# Microcontroller.net
KiCad netlist of a schematic drawn in Altium Designer
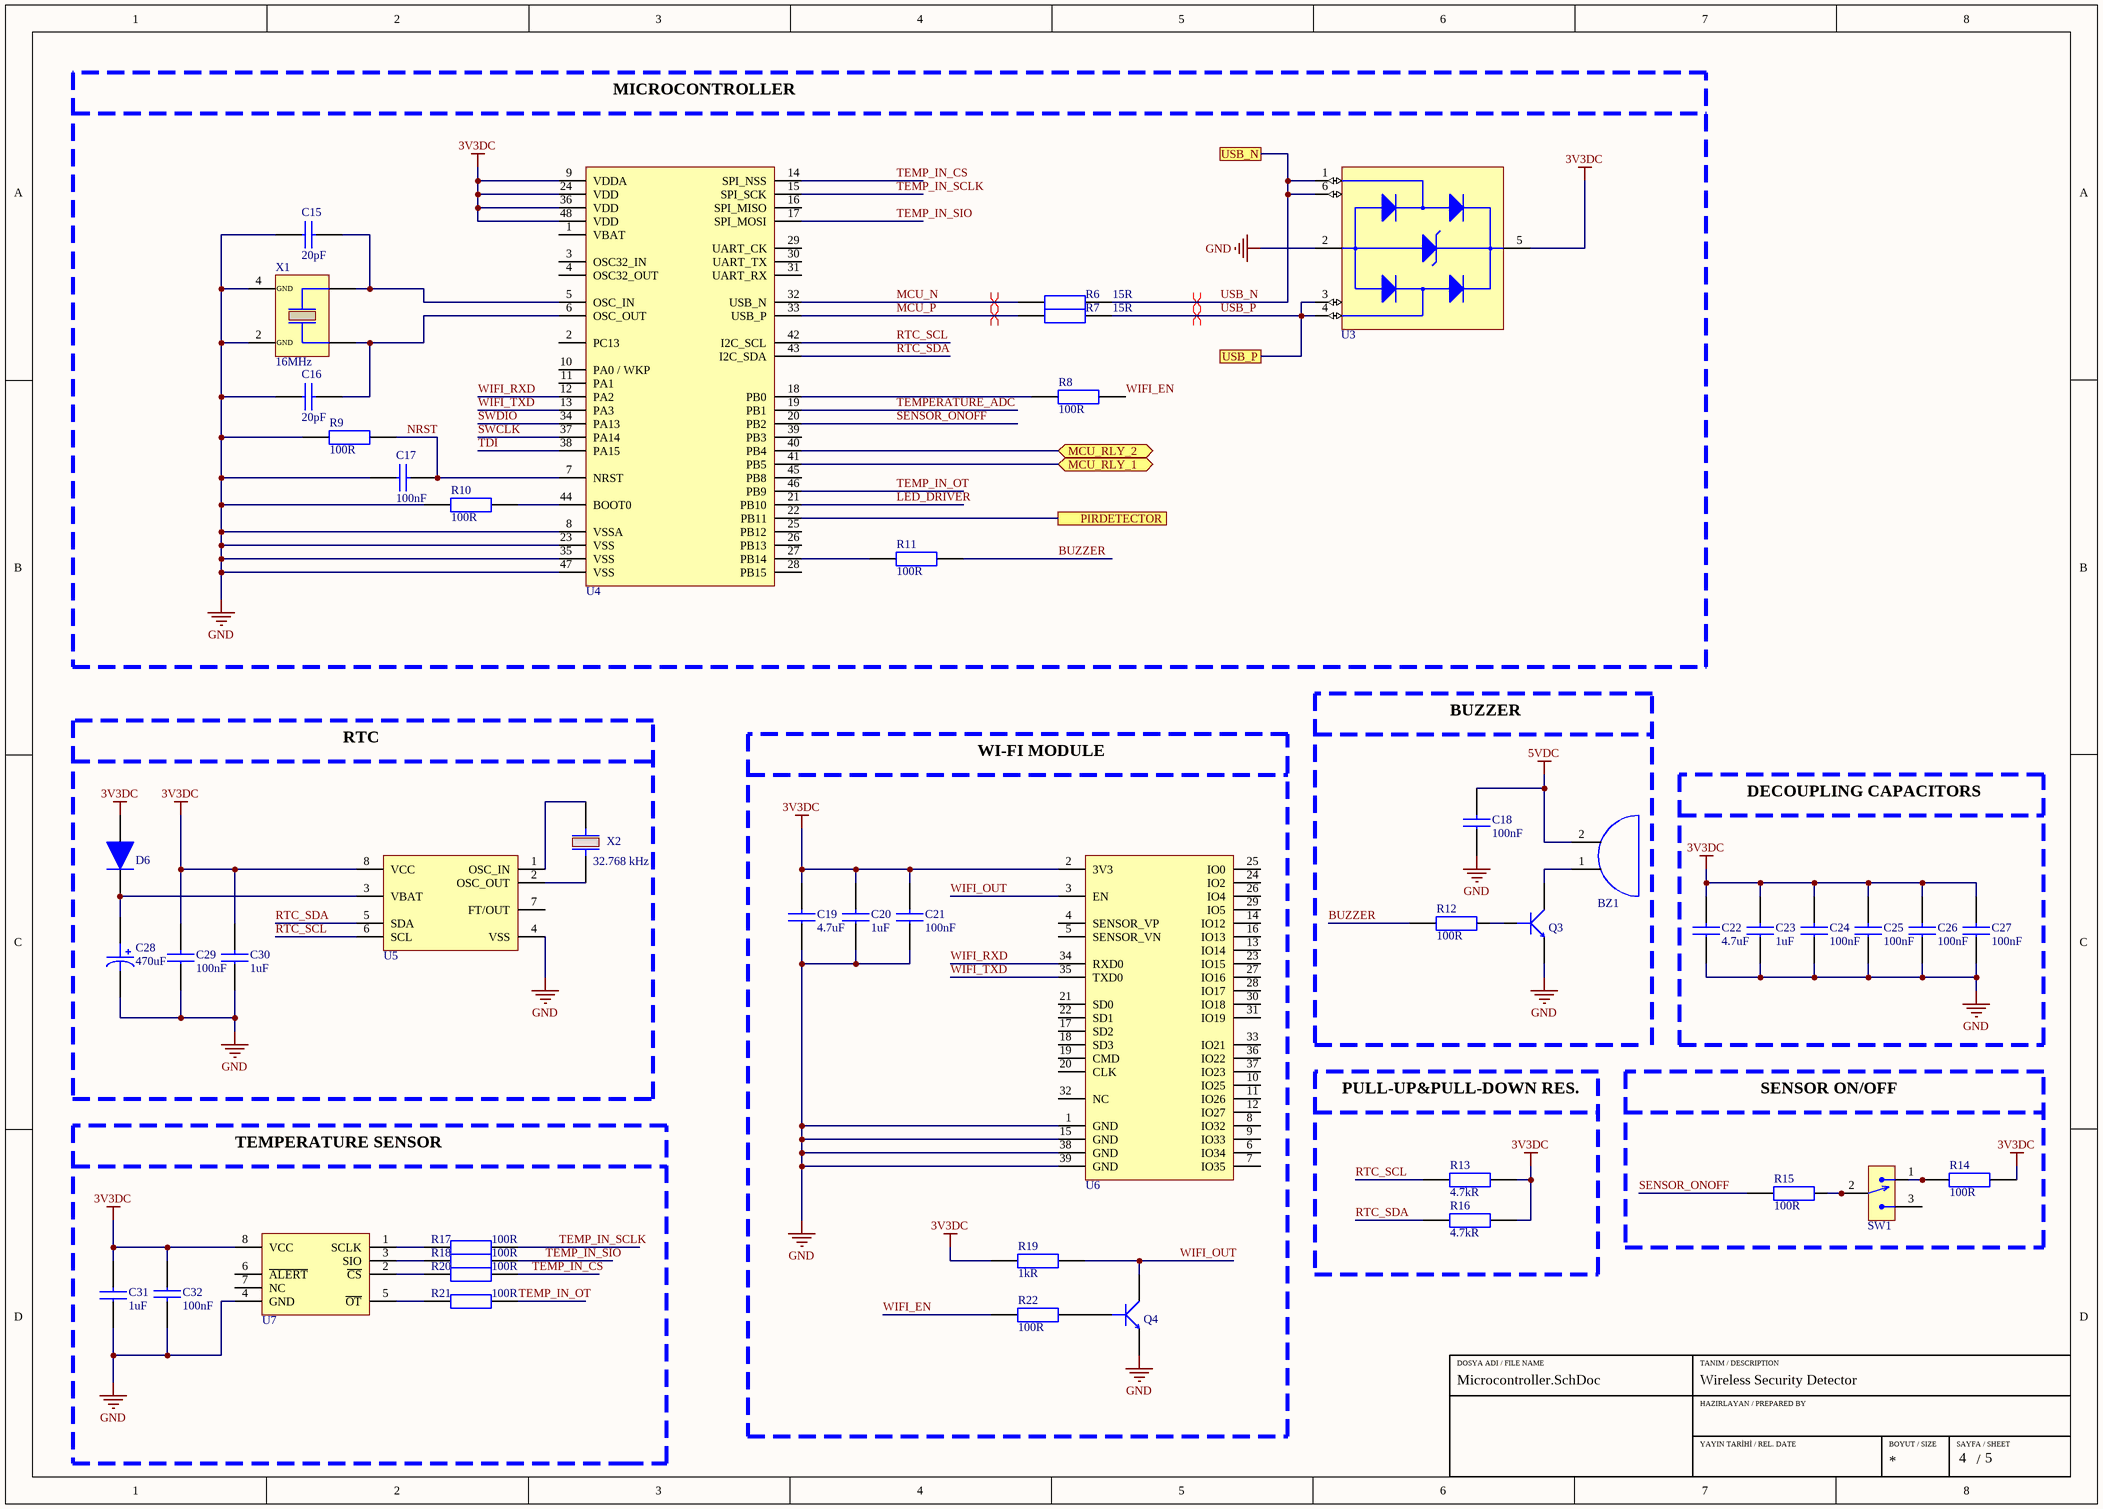
[diagram p0: Microcontroller.SchDoc]

(export (version "E")
  (design (tool "Eeschema 10.0.6"))
  (components
    (comp (ref "BZ1")
      (value "CMI-9605IC-0580T")
      (footprint "CMI-9605IC")
      (description "Buzzers Indicator, Internally Driven Magnetic 5V 30mA 2.7kHz 80dB @ 5V, 10cm Through Hole PC Pins")
      (fields (field (name "MANUFACTURER") "CUI Devices") (field (name "DESIGNED BY") "BERK"))
      (libsource (lib "SECURITY_CAM") (part "CMI-9605IC-0580T"))
    )
    (comp (ref "C15")
      (value "CL10C200JB8NNNC")
      (footprint "CAP_0603")
      (description "CAP CER 20pF %5 0603 SMD")
      (fields
        (field (name "MANUFACTURER") "Samsung")
        (field (name "TOLERANCE") "5%")
        (field (name "CAPACITANCE") "20pF")
        (field (name "DESIGNED BY") "BERK")
      )
      (libsource (lib "SECURITY_CAM") (part "CAP CER 20pF 0603"))
    )
    (comp (ref "C16")
      (value "CL10C200JB8NNNC")
      (footprint "CAP_0603")
      (description "CAP CER 20pF %5 0603 SMD")
      (fields
        (field (name "MANUFACTURER") "Samsung")
        (field (name "TOLERANCE") "5%")
        (field (name "CAPACITANCE") "20pF")
        (field (name "DESIGNED BY") "BERK")
      )
      (libsource (lib "SECURITY_CAM") (part "CAP CER 20pF 0603"))
    )
    (comp (ref "C17")
      (value "C0603C104K5RACTU")
      (footprint "CAP_0603")
      (description "CAP CER 100nF %10 0603 SMD")
      (fields
        (field (name "MANUFACTURER") "KEMET")
        (field (name "TOLERANCE") "10%")
        (field (name "CAPACITANCE") "100nF")
        (field (name "DESIGNED BY") "BERK")
      )
      (libsource (lib "SECURITY_CAM") (part "CAP CER 100nF 0603"))
    )
    (comp (ref "C18")
      (value "CL21B104KBCNNNC")
      (footprint "CAP_0805")
      (description "CAP CER 100nF %10 0805")
      (fields
        (field (name "MANUFACTURER") "Samsung")
        (field (name "TOLERANCE") "10%")
        (field (name "CAPACITANCE") "100nF")
        (field (name "DESIGNED BY") "BERK")
      )
      (libsource (lib "SECURITY_CAM") (part "CAP CER 100nF 0805"))
    )
    (comp (ref "C19")
      (value "CL21A475KAQNNNE")
      (footprint "CAP_0805")
      (description "CAP CER 4.7uF %10 0805")
      (fields
        (field (name "MANUFACTURER") "Samsung")
        (field (name "TOLERANCE") "10%")
        (field (name "CAPACITANCE") "4.7uF")
        (field (name "DESIGNED BY") "BERK")
      )
      (libsource (lib "SECURITY_CAM") (part "CAP CER 4.7uF 0805"))
    )
    (comp (ref "C20")
      (value "CL21B105KBFNNNE")
      (footprint "CAP_0805")
      (description "CAP CER 1uF %10 0805")
      (fields
        (field (name "MANUFACTURER") "Samsung")
        (field (name "TOLERANCE") "10%")
        (field (name "CAPACITANCE") "1uF")
        (field (name "DESIGNED BY") "BERK")
      )
      (libsource (lib "SECURITY_CAM") (part "CAP CER 1uF 0805"))
    )
    (comp (ref "C21")
      (value "CL21B104KBCNNNC")
      (footprint "CAP_0805")
      (description "CAP CER 100nF %10 0805")
      (fields
        (field (name "MANUFACTURER") "Samsung")
        (field (name "TOLERANCE") "10%")
        (field (name "CAPACITANCE") "100nF")
        (field (name "DESIGNED BY") "BERK")
      )
      (libsource (lib "SECURITY_CAM") (part "CAP CER 100nF 0805"))
    )
    (comp (ref "C22")
      (value "CL21A475KAQNNNE")
      (footprint "CAP_0805")
      (description "CAP CER 4.7uF %10 0805")
      (fields
        (field (name "MANUFACTURER") "Samsung")
        (field (name "TOLERANCE") "10%")
        (field (name "CAPACITANCE") "4.7uF")
        (field (name "DESIGNED BY") "BERK")
      )
      (libsource (lib "SECURITY_CAM") (part "CAP CER 4.7uF 0805"))
    )
    (comp (ref "C23")
      (value "CL21B105KBFNNNE")
      (footprint "CAP_0805")
      (description "CAP CER 1uF %10 0805")
      (fields
        (field (name "MANUFACTURER") "Samsung")
        (field (name "TOLERANCE") "10%")
        (field (name "CAPACITANCE") "1uF")
        (field (name "DESIGNED BY") "BERK")
      )
      (libsource (lib "SECURITY_CAM") (part "CAP CER 1uF 0805"))
    )
    (comp (ref "C24")
      (value "C0603C104K5RACTU")
      (footprint "CAP_0603")
      (description "CAP CER 100nF %10 0603 SMD")
      (fields
        (field (name "MANUFACTURER") "KEMET")
        (field (name "TOLERANCE") "10%")
        (field (name "CAPACITANCE") "100nF")
        (field (name "DESIGNED BY") "BERK")
      )
      (libsource (lib "SECURITY_CAM") (part "CAP CER 100nF 0603"))
    )
    (comp (ref "C25")
      (value "C0603C104K5RACTU")
      (footprint "CAP_0603")
      (description "CAP CER 100nF %10 0603 SMD")
      (fields
        (field (name "MANUFACTURER") "KEMET")
        (field (name "TOLERANCE") "10%")
        (field (name "CAPACITANCE") "100nF")
        (field (name "DESIGNED BY") "BERK")
      )
      (libsource (lib "SECURITY_CAM") (part "CAP CER 100nF 0603"))
    )
    (comp (ref "C26")
      (value "C0603C104K5RACTU")
      (footprint "CAP_0603")
      (description "CAP CER 100nF %10 0603 SMD")
      (fields
        (field (name "MANUFACTURER") "KEMET")
        (field (name "TOLERANCE") "10%")
        (field (name "CAPACITANCE") "100nF")
        (field (name "DESIGNED BY") "BERK")
      )
      (libsource (lib "SECURITY_CAM") (part "CAP CER 100nF 0603"))
    )
    (comp (ref "C27")
      (value "C0603C104K5RACTU")
      (footprint "CAP_0603")
      (description "CAP CER 100nF %10 0603 SMD")
      (fields
        (field (name "MANUFACTURER") "KEMET")
        (field (name "TOLERANCE") "10%")
        (field (name "CAPACITANCE") "100nF")
        (field (name "DESIGNED BY") "BERK")
      )
      (libsource (lib "SECURITY_CAM") (part "CAP CER 100nF 0603"))
    )
    (comp (ref "C28")
      (value "ESH477M050AH4AA")
      (footprint "CAP_RADIAL_D10_P5")
      (description "CAP ALU ELEC 470uF 50V RADIAL")
      (fields
        (field (name "MANUFACTURER") "KEMET")
        (field (name "TOLERANCE") "20%")
        (field (name "CAPACITANCE") "470uF")
        (field (name "DESIGNED BY") "BERK")
      )
      (libsource (lib "SECURITY_CAM") (part "CAP ALU ELEC 470uF 50V"))
    )
    (comp (ref "C29")
      (value "CL21B104KBCNNNC")
      (footprint "CAP_0805")
      (description "CAP CER 100nF %10 0805")
      (fields
        (field (name "MANUFACTURER") "Samsung")
        (field (name "TOLERANCE") "10%")
        (field (name "CAPACITANCE") "100nF")
        (field (name "DESIGNED BY") "BERK")
      )
      (libsource (lib "SECURITY_CAM") (part "CAP CER 100nF 0805"))
    )
    (comp (ref "C30")
      (value "CL21B105KBFNNNE")
      (footprint "CAP_0805")
      (description "CAP CER 1uF %10 0805")
      (fields
        (field (name "MANUFACTURER") "Samsung")
        (field (name "TOLERANCE") "10%")
        (field (name "CAPACITANCE") "1uF")
        (field (name "DESIGNED BY") "BERK")
      )
      (libsource (lib "SECURITY_CAM") (part "CAP CER 1uF 0805"))
    )
    (comp (ref "C31")
      (value "CL21B105KBFNNNE")
      (footprint "CAP_0805")
      (description "CAP CER 1uF %10 0805")
      (fields
        (field (name "MANUFACTURER") "Samsung")
        (field (name "TOLERANCE") "10%")
        (field (name "CAPACITANCE") "1uF")
        (field (name "DESIGNED BY") "BERK")
      )
      (libsource (lib "SECURITY_CAM") (part "CAP CER 1uF 0805"))
    )
    (comp (ref "C32")
      (value "CL21B104KBCNNNC")
      (footprint "CAP_0805")
      (description "CAP CER 100nF %10 0805")
      (fields
        (field (name "MANUFACTURER") "Samsung")
        (field (name "TOLERANCE") "10%")
        (field (name "CAPACITANCE") "100nF")
        (field (name "DESIGNED BY") "BERK")
      )
      (libsource (lib "SECURITY_CAM") (part "CAP CER 100nF 0805"))
    )
    (comp (ref "D6")
      (value "1N4148WS")
      (footprint "SOD323F")
      (description "Diode, Single, 75 V, 150 mA, 1 V, 4 ns")
      (fields
        (field (name "MANUFACTURER") "ON Semiconductor / Fairchild")
        (field (name "DESIGNED BY") "BERK")
      )
      (libsource (lib "SECURITY_CAM") (part "1N4148WS"))
    )
    (comp (ref "Q3")
      (value "MMBT3904-7-F")
      (footprint "SOT-23F")
      (description "Transistor General Purpose BJT NPN 40 Volt 0.2A Automotive 3-Pin SOT-23")
      (fields (field (name "MANUFACTURER") "Diodes Zetex") (field (name "DESIGNED BY") "BERK"))
      (libsource (lib "SECURITY_CAM") (part "MMBT3904-7-F"))
    )
    (comp (ref "Q4")
      (value "MMBT3904-7-F")
      (footprint "SOT-23F")
      (description "Transistor General Purpose BJT NPN 40 Volt 0.2A Automotive 3-Pin SOT-23")
      (fields (field (name "MANUFACTURER") "Diodes Zetex") (field (name "DESIGNED BY") "BERK"))
      (libsource (lib "SECURITY_CAM") (part "MMBT3904-7-F"))
    )
    (comp (ref "R6")
      (value "RC0603JR-0715RL")
      (footprint "RES_0603")
      (description "RES 15 %5 OHM 0603 SMD")
      (fields
        (field (name "MANUFACTURER") "Yageo")
        (field (name "TOLERANCE") "5%")
        (field (name "RESISTANCE") "15R")
        (field (name "DESIGNED BY") "BERK")
      )
      (libsource (lib "SECURITY_CAM") (part "RES 15 OHM 0603"))
    )
    (comp (ref "R7")
      (value "RC0603JR-0715RL")
      (footprint "RES_0603")
      (description "RES 15 %5 OHM 0603 SMD")
      (fields
        (field (name "MANUFACTURER") "Yageo")
        (field (name "TOLERANCE") "5%")
        (field (name "RESISTANCE") "15R")
        (field (name "DESIGNED BY") "BERK")
      )
      (libsource (lib "SECURITY_CAM") (part "RES 15 OHM 0603"))
    )
    (comp (ref "R8")
      (value "RC0603JR-07100RL")
      (footprint "RES_0603")
      (description "RES 100 %5 OHM 0603 SMD")
      (fields
        (field (name "MANUFACTURER") "Yageo")
        (field (name "TOLERANCE") "5%")
        (field (name "RESISTANCE") "100R")
        (field (name "DESIGNED BY") "BERK")
      )
      (libsource (lib "SECURITY_CAM") (part "RES 100 OHM 0603"))
    )
    (comp (ref "R9")
      (value "RC0603JR-07100RL")
      (footprint "RES_0603")
      (description "RES 100 %5 OHM 0603 SMD")
      (fields
        (field (name "MANUFACTURER") "Yageo")
        (field (name "TOLERANCE") "5%")
        (field (name "RESISTANCE") "100R")
        (field (name "DESIGNED BY") "BERK")
      )
      (libsource (lib "SECURITY_CAM") (part "RES 100 OHM 0603"))
    )
    (comp (ref "R10")
      (value "RC0603JR-07100RL")
      (footprint "RES_0603")
      (description "RES 100 %5 OHM 0603 SMD")
      (fields
        (field (name "MANUFACTURER") "Yageo")
        (field (name "TOLERANCE") "5%")
        (field (name "RESISTANCE") "100R")
        (field (name "DESIGNED BY") "BERK")
      )
      (libsource (lib "SECURITY_CAM") (part "RES 100 OHM 0603"))
    )
    (comp (ref "R11")
      (value "RC0603JR-07100RL")
      (footprint "RES_0603")
      (description "RES 100 %5 OHM 0603 SMD")
      (fields
        (field (name "MANUFACTURER") "Yageo")
        (field (name "TOLERANCE") "5%")
        (field (name "RESISTANCE") "100R")
        (field (name "DESIGNED BY") "BERK")
      )
      (libsource (lib "SECURITY_CAM") (part "RES 100 OHM 0603"))
    )
    (comp (ref "R12")
      (value "RC0603JR-07100RL")
      (footprint "RES_0603")
      (description "RES 100 %5 OHM 0603 SMD")
      (fields
        (field (name "MANUFACTURER") "Yageo")
        (field (name "TOLERANCE") "5%")
        (field (name "RESISTANCE") "100R")
        (field (name "DESIGNED BY") "BERK")
      )
      (libsource (lib "SECURITY_CAM") (part "RES 100 OHM 0603"))
    )
    (comp (ref "R13")
      (value "RC0603JR-074K7L")
      (footprint "RES_0603")
      (description "RES 4K7 %5 OHM 0603 SMD")
      (fields
        (field (name "MANUFACTURER") "Yageo")
        (field (name "TOLERANCE") "5%")
        (field (name "RESISTANCE") "4.7kR")
        (field (name "DESIGNED BY") "BERK")
      )
      (libsource (lib "SECURITY_CAM") (part "RES 4K7 OHM 0603"))
    )
    (comp (ref "R14")
      (value "RC0603JR-07100RL")
      (footprint "RES_0603")
      (description "RES 100 %5 OHM 0603 SMD")
      (fields
        (field (name "MANUFACTURER") "Yageo")
        (field (name "TOLERANCE") "5%")
        (field (name "RESISTANCE") "100R")
        (field (name "DESIGNED BY") "BERK")
      )
      (libsource (lib "SECURITY_CAM") (part "RES 100 OHM 0603"))
    )
    (comp (ref "R15")
      (value "RC0603JR-07100RL")
      (footprint "RES_0603")
      (description "RES 100 %5 OHM 0603 SMD")
      (fields
        (field (name "MANUFACTURER") "Yageo")
        (field (name "TOLERANCE") "5%")
        (field (name "RESISTANCE") "100R")
        (field (name "DESIGNED BY") "BERK")
      )
      (libsource (lib "SECURITY_CAM") (part "RES 100 OHM 0603"))
    )
    (comp (ref "R16")
      (value "RC0603JR-074K7L")
      (footprint "RES_0603")
      (description "RES 4K7 %5 OHM 0603 SMD")
      (fields
        (field (name "MANUFACTURER") "Yageo")
        (field (name "TOLERANCE") "5%")
        (field (name "RESISTANCE") "4.7kR")
        (field (name "DESIGNED BY") "BERK")
      )
      (libsource (lib "SECURITY_CAM") (part "RES 4K7 OHM 0603"))
    )
    (comp (ref "R17")
      (value "RC0603JR-07100RL")
      (footprint "RES_0603")
      (description "RES 100 %5 OHM 0603 SMD")
      (fields
        (field (name "MANUFACTURER") "Yageo")
        (field (name "TOLERANCE") "5%")
        (field (name "RESISTANCE") "100R")
        (field (name "DESIGNED BY") "BERK")
      )
      (libsource (lib "SECURITY_CAM") (part "RES 100 OHM 0603"))
    )
    (comp (ref "R18")
      (value "RC0603JR-07100RL")
      (footprint "RES_0603")
      (description "RES 100 %5 OHM 0603 SMD")
      (fields
        (field (name "MANUFACTURER") "Yageo")
        (field (name "TOLERANCE") "5%")
        (field (name "RESISTANCE") "100R")
        (field (name "DESIGNED BY") "BERK")
      )
      (libsource (lib "SECURITY_CAM") (part "RES 100 OHM 0603"))
    )
    (comp (ref "R19")
      (value "RC0603FR-0710KL")
      (footprint "RES_0603")
      (description "RES 1K %1 OHM 0603 SMD")
      (fields
        (field (name "MANUFACTURER") "Yageo")
        (field (name "MANUFACTURER PART NUMBER") "RC0603JR-071KL")
        (field (name "RESISTANCE") "1kR")
        (field (name "DESIGNED BY") "BERK")
      )
      (libsource (lib "SECURITY_CAM") (part "RES 1K OHM 0603"))
    )
    (comp (ref "R20")
      (value "RC0603JR-07100RL")
      (footprint "RES_0603")
      (description "RES 100 %5 OHM 0603 SMD")
      (fields
        (field (name "MANUFACTURER") "Yageo")
        (field (name "TOLERANCE") "5%")
        (field (name "RESISTANCE") "100R")
        (field (name "DESIGNED BY") "BERK")
      )
      (libsource (lib "SECURITY_CAM") (part "RES 100 OHM 0603"))
    )
    (comp (ref "R21")
      (value "RC0603JR-07100RL")
      (footprint "RES_0603")
      (description "RES 100 %5 OHM 0603 SMD")
      (fields
        (field (name "MANUFACTURER") "Yageo")
        (field (name "TOLERANCE") "5%")
        (field (name "RESISTANCE") "100R")
        (field (name "DESIGNED BY") "BERK")
      )
      (libsource (lib "SECURITY_CAM") (part "RES 100 OHM 0603"))
    )
    (comp (ref "R22")
      (value "RC0603JR-07100RL")
      (footprint "RES_0603")
      (description "RES 100 %5 OHM 0603 SMD")
      (fields
        (field (name "MANUFACTURER") "Yageo")
        (field (name "TOLERANCE") "5%")
        (field (name "RESISTANCE") "100R")
        (field (name "DESIGNED BY") "BERK")
      )
      (libsource (lib "SECURITY_CAM") (part "RES 100 OHM 0603"))
    )
    (comp (ref "SW1")
      (value "EG1215AA")
      (footprint "EG1215AA")
      (description "Slide Switch, SPDT, 0.025A, 24V, SMD")
      (fields
        (field (name "MANUFACTURER") "E-Switch")
        (field (name "TOLERANCE") "4.95%")
        (field (name "DESIGNED BY") "BERK")
      )
      (libsource (lib "SECURITY_CAM") (part "EG1215AA"))
    )
    (comp (ref "U3")
      (value "USBLC6-2SC6")
      (footprint "SOT23-6L")
      (description "TVS DIODE 5.25V 17V SOT23-6")
      (fields (field (name "MANUFACTURER") "STMicroelectronics") (field (name "DESIGNED BY") "BERK"))
      (libsource (lib "SECURITY_CAM") (part "USB PROTECTION"))
    )
    (comp (ref "U4")
      (value "STM32F103C6T6A")
      (footprint "LQFP-48")
      (description "MCU 32-bit STM32F ARM Cortex M3 RISC 32KB Flash 2.5V/3.3V 48-Pin LQFP Tray")
      (fields (field (name "MANUFACTURER") "STMicroelectronics") (field (name "DESIGNED BY") "BERK"))
      (libsource (lib "SECURITY_CAM") (part "STM32F103C6T6A"))
    )
    (comp (ref "U5")
      (value "M41T00M6F")
      (footprint "SOIC8")
      (description "IC RTC CLK/CALENDAR I2C 8-SOIC")
      (fields (field (name "MANUFACTURER") "STMicroelectronics") (field (name "DESIGNED BY") "BERK"))
      (libsource (lib "SECURITY_CAM") (part "M41T00M6F"))
    )
    (comp (ref "U6")
      (value "ESP32-WROOM-32")
      (footprint "ESP32-32")
      (description "SMD MODULE, ESP32-D0WDQ6, 32MBIT")
      (fields (field (name "MANUFACTURER") "Espressif Systems") (field (name "DESIGNED BY") "BERK"))
      (libsource (lib "SECURITY_CAM") (part "ESP32-WROOM-32"))
    )
    (comp (ref "U7")
      (value "MAX6662")
      (footprint "SOIC8")
      (description "SENSOR TEMPERATURE SPI 8SOIC")
      (fields
        (field (name "MANUFACTURER") "Maxim")
        (field (name "MANUFACTURER PART NUMBER") "MAX6662MSA+")
        (field (name "DESIGNED BY") "BERK")
      )
      (libsource (lib "SECURITY_CAM") (part "MAX6662"))
    )
    (comp (ref "X1")
      (value "ECS-160-20-30B-TR")
      (footprint "ECS")
      (description "CRYSTAL 16.0000MHZ 20PF SMD")
      (fields
        (field (name "MANUFACTURER") "ECS International")
        (field (name "TOLERANCE") "50ppm")
        (field (name "FREQUENCY") "16MHz")
        (field (name "DESIGNED BY") "BERK")
      )
      (libsource (lib "SECURITY_CAM") (part "CRYSTAL 16MHz"))
    )
    (comp (ref "X2")
      (value "ABS05-32.768KHZ-T")
      (footprint "ABS05")
      (description "Crystal, 32.768 kHz, SMD, 1.6mm x 1mm, 12.5 pF, 20 ppm, ABS05 Series")
      (fields
        (field (name "MANUFACTURER") "Abracon")
        (field (name "TOLERANCE") "20ppm")
        (field (name "OPERATING FREQUENCY") "32.768 kHz")
        (field (name "DESIGNED BY") "BERK")
      )
      (libsource (lib "SECURITY_CAM") (part "CRYSTAL 32768kHZ"))
    )
  )
  (nets
    (net (code "1") (name "/BUZZER") (class "Default")
      (node (ref "R11") (pin "2") (pinfunction "2_2") (pintype "passive"))
      (node (ref "R12") (pin "1") (pinfunction "1_1") (pintype "passive"))
    )
    (net (code "2") (name "/LED_DRIVER") (class "Default")
      (node (ref "U4") (pin "21") (pinfunction "PB10_21") (pintype "passive"))
    )
    (net (code "3") (name "/MCU_N") (class "Default")
      (node (ref "R6") (pin "1") (pinfunction "1_1") (pintype "passive"))
      (node (ref "U4") (pin "32") (pinfunction "USB_N_32") (pintype "passive"))
    )
    (net (code "4") (name "/MCU_P") (class "Default")
      (node (ref "R7") (pin "1") (pinfunction "1_1") (pintype "passive"))
      (node (ref "U4") (pin "33") (pinfunction "USB_P_33") (pintype "passive"))
    )
    (net (code "5") (name "/MCU_RLY_1") (class "Default")
      (node (ref "U4") (pin "41") (pinfunction "PB5_41") (pintype "passive"))
    )
    (net (code "6") (name "/MCU_RLY_2") (class "Default")
      (node (ref "U4") (pin "40") (pinfunction "PB4_40") (pintype "passive"))
    )
    (net (code "7") (name "/NRST") (class "Default")
      (node (ref "C17") (pin "2") (pinfunction "2_2") (pintype "passive"))
      (node (ref "R9") (pin "2") (pinfunction "2_2") (pintype "passive"))
      (node (ref "U4") (pin "7") (pinfunction "NRST_7") (pintype "passive"))
    )
    (net (code "8") (name "/PIRDETECTOR") (class "Default")
      (node (ref "U4") (pin "22") (pinfunction "PB11_22") (pintype "passive"))
    )
    (net (code "9") (name "/RTC_SCL") (class "Default")
      (node (ref "R13") (pin "1") (pinfunction "1_1") (pintype "passive"))
      (node (ref "U4") (pin "42") (pinfunction "I2C_SCL_42") (pintype "passive"))
      (node (ref "U5") (pin "6") (pinfunction "SCL_6") (pintype "passive"))
    )
    (net (code "10") (name "/RTC_SDA") (class "Default")
      (node (ref "R16") (pin "1") (pinfunction "1_1") (pintype "passive"))
      (node (ref "U4") (pin "43") (pinfunction "I2C_SDA_43") (pintype "passive"))
      (node (ref "U5") (pin "5") (pinfunction "SDA_5") (pintype "passive"))
    )
    (net (code "11") (name "/SENSOR_ONOFF") (class "Default")
      (node (ref "R15") (pin "1") (pinfunction "1_1") (pintype "passive"))
      (node (ref "U4") (pin "20") (pinfunction "PB2_20") (pintype "passive"))
    )
    (net (code "12") (name "/SWCLK") (class "Default")
      (node (ref "U4") (pin "37") (pinfunction "PA14_37") (pintype "passive"))
    )
    (net (code "13") (name "/SWDIO") (class "Default")
      (node (ref "U4") (pin "34") (pinfunction "PA13_34") (pintype "passive"))
    )
    (net (code "14") (name "/TDI") (class "Default")
      (node (ref "U4") (pin "38") (pinfunction "PA15_38") (pintype "passive"))
    )
    (net (code "15") (name "/TEMPERATURE_ADC") (class "Default")
      (node (ref "U4") (pin "19") (pinfunction "PB1_19") (pintype "passive"))
    )
    (net (code "16") (name "/TEMP_IN_CS") (class "Default")
      (node (ref "R20") (pin "2") (pinfunction "2_2") (pintype "passive"))
      (node (ref "U4") (pin "14") (pinfunction "SPI_NSS_14") (pintype "passive"))
    )
    (net (code "17") (name "/TEMP_IN_OT") (class "Default")
      (node (ref "R21") (pin "2") (pinfunction "2_2") (pintype "passive"))
      (node (ref "U4") (pin "46") (pinfunction "PB9_46") (pintype "passive"))
    )
    (net (code "18") (name "/TEMP_IN_SCLK") (class "Default")
      (node (ref "R17") (pin "2") (pinfunction "2_2") (pintype "passive"))
      (node (ref "U4") (pin "15") (pinfunction "SPI_SCK_15") (pintype "passive"))
    )
    (net (code "19") (name "/TEMP_IN_SIO") (class "Default")
      (node (ref "R18") (pin "2") (pinfunction "2_2") (pintype "passive"))
      (node (ref "U4") (pin "17") (pinfunction "SPI_MOSI_17") (pintype "passive"))
    )
    (net (code "20") (name "/USB_N") (class "Default")
      (node (ref "R6") (pin "2") (pinfunction "2_2") (pintype "passive"))
      (node (ref "U3") (pin "1") (pinfunction "I/O1_1") (pintype "bidirectional"))
      (node (ref "U3") (pin "6") (pinfunction "I/O1_6") (pintype "bidirectional"))
    )
    (net (code "21") (name "/USB_P") (class "Default")
      (node (ref "R7") (pin "2") (pinfunction "2_2") (pintype "passive"))
      (node (ref "U3") (pin "3") (pinfunction "I/O2_3") (pintype "bidirectional"))
      (node (ref "U3") (pin "4") (pinfunction "I/O2_4") (pintype "bidirectional"))
    )
    (net (code "22") (name "/WIFI_EN") (class "Default")
      (node (ref "R22") (pin "1") (pinfunction "1_1") (pintype "passive"))
      (node (ref "R8") (pin "2") (pinfunction "2_2") (pintype "passive"))
    )
    (net (code "23") (name "/WIFI_OUT") (class "Default")
      (node (ref "Q4") (pin "3") (pinfunction "C_3") (pintype "power_in"))
      (node (ref "R19") (pin "2") (pinfunction "2_2") (pintype "passive"))
      (node (ref "U6") (pin "3") (pinfunction "EN_3") (pintype "passive"))
    )
    (net (code "24") (name "/WIFI_RXD") (class "Default")
      (node (ref "U4") (pin "12") (pinfunction "PA2_12") (pintype "passive"))
      (node (ref "U6") (pin "34") (pinfunction "RXD0_34") (pintype "passive"))
    )
    (net (code "25") (name "/WIFI_TXD") (class "Default")
      (node (ref "U4") (pin "13") (pinfunction "PA3_13") (pintype "passive"))
      (node (ref "U6") (pin "35") (pinfunction "TXD0_35") (pintype "passive"))
    )
    (net (code "26") (name "3V3DC") (class "Default")
      (node (ref "C19") (pin "2") (pinfunction "2_2") (pintype "passive"))
      (node (ref "C20") (pin "2") (pinfunction "2_2") (pintype "passive"))
      (node (ref "C21") (pin "2") (pinfunction "2_2") (pintype "passive"))
      (node (ref "C22") (pin "2") (pinfunction "2_2") (pintype "passive"))
      (node (ref "C23") (pin "2") (pinfunction "2_2") (pintype "passive"))
      (node (ref "C24") (pin "2") (pinfunction "2_2") (pintype "passive"))
      (node (ref "C25") (pin "2") (pinfunction "2_2") (pintype "passive"))
      (node (ref "C26") (pin "2") (pinfunction "2_2") (pintype "passive"))
      (node (ref "C27") (pin "2") (pinfunction "2_2") (pintype "passive"))
      (node (ref "C29") (pin "2") (pinfunction "2_2") (pintype "passive"))
      (node (ref "C30") (pin "2") (pinfunction "2_2") (pintype "passive"))
      (node (ref "C31") (pin "2") (pinfunction "2_2") (pintype "passive"))
      (node (ref "C32") (pin "1") (pinfunction "1_1") (pintype "passive"))
      (node (ref "D6") (pin "2") (pinfunction "2_2") (pintype "power_in"))
      (node (ref "R13") (pin "2") (pinfunction "2_2") (pintype "passive"))
      (node (ref "R14") (pin "2") (pinfunction "2_2") (pintype "passive"))
      (node (ref "R16") (pin "2") (pinfunction "2_2") (pintype "passive"))
      (node (ref "R19") (pin "1") (pinfunction "1_1") (pintype "passive"))
      (node (ref "U3") (pin "5") (pinfunction "VBUS_5") (pintype "power_in"))
      (node (ref "U4") (pin "24") (pinfunction "VDD_24") (pintype "passive"))
      (node (ref "U4") (pin "36") (pinfunction "VDD_36") (pintype "passive"))
      (node (ref "U4") (pin "48") (pinfunction "VDD_48") (pintype "passive"))
      (node (ref "U4") (pin "9") (pinfunction "VDDA_9") (pintype "passive"))
      (node (ref "U5") (pin "8") (pinfunction "VCC_8") (pintype "passive"))
      (node (ref "U6") (pin "2") (pinfunction "3V3_2") (pintype "passive"))
      (node (ref "U7") (pin "8") (pinfunction "VCC_8") (pintype "passive"))
    )
    (net (code "27") (name "5VDC") (class "Default")
      (node (ref "BZ1") (pin "2") (pinfunction "2_2") (pintype "passive"))
      (node (ref "C18") (pin "2") (pinfunction "2_2") (pintype "passive"))
    )
    (net (code "28") (name "GND") (class "Default")
      (node (ref "C15") (pin "1") (pinfunction "1_1") (pintype "passive"))
      (node (ref "C16") (pin "1") (pinfunction "1_1") (pintype "passive"))
      (node (ref "C17") (pin "1") (pinfunction "1_1") (pintype "passive"))
      (node (ref "C18") (pin "1") (pinfunction "1_1") (pintype "passive"))
      (node (ref "C19") (pin "1") (pinfunction "1_1") (pintype "passive"))
      (node (ref "C20") (pin "1") (pinfunction "1_1") (pintype "passive"))
      (node (ref "C21") (pin "1") (pinfunction "1_1") (pintype "passive"))
      (node (ref "C22") (pin "1") (pinfunction "1_1") (pintype "passive"))
      (node (ref "C23") (pin "1") (pinfunction "1_1") (pintype "passive"))
      (node (ref "C24") (pin "1") (pinfunction "1_1") (pintype "passive"))
      (node (ref "C25") (pin "1") (pinfunction "1_1") (pintype "passive"))
      (node (ref "C26") (pin "1") (pinfunction "1_1") (pintype "passive"))
      (node (ref "C27") (pin "1") (pinfunction "1_1") (pintype "passive"))
      (node (ref "C28") (pin "2") (pinfunction "2_2") (pintype "passive"))
      (node (ref "C29") (pin "1") (pinfunction "1_1") (pintype "passive"))
      (node (ref "C30") (pin "1") (pinfunction "1_1") (pintype "passive"))
      (node (ref "C31") (pin "1") (pinfunction "1_1") (pintype "passive"))
      (node (ref "C32") (pin "2") (pinfunction "2_2") (pintype "passive"))
      (node (ref "Q3") (pin "2") (pinfunction "E_2") (pintype "power_in"))
      (node (ref "Q4") (pin "2") (pinfunction "E_2") (pintype "power_in"))
      (node (ref "R10") (pin "1") (pinfunction "1_1") (pintype "passive"))
      (node (ref "R9") (pin "1") (pinfunction "1_1") (pintype "passive"))
      (node (ref "U3") (pin "2") (pinfunction "GND_2") (pintype "power_in"))
      (node (ref "U4") (pin "23") (pinfunction "VSS_23") (pintype "passive"))
      (node (ref "U4") (pin "35") (pinfunction "VSS_35") (pintype "passive"))
      (node (ref "U4") (pin "47") (pinfunction "VSS_47") (pintype "passive"))
      (node (ref "U4") (pin "8") (pinfunction "VSSA_8") (pintype "passive"))
      (node (ref "U5") (pin "4") (pinfunction "VSS_4") (pintype "passive"))
      (node (ref "U6") (pin "1") (pinfunction "GND_1") (pintype "passive"))
      (node (ref "U6") (pin "15") (pinfunction "GND_15") (pintype "passive"))
      (node (ref "U6") (pin "38") (pinfunction "GND_38") (pintype "passive"))
      (node (ref "U6") (pin "39") (pinfunction "GND_39") (pintype "passive"))
      (node (ref "U7") (pin "4") (pinfunction "GND_4") (pintype "passive"))
      (node (ref "X1") (pin "2") (pinfunction "GND_2") (pintype "passive"))
      (node (ref "X1") (pin "4") (pinfunction "GND_4") (pintype "passive"))
    )
    (net (code "29") (name "Net-(Q3-B)") (class "Default")
      (node (ref "Q3") (pin "1") (pinfunction "B_1") (pintype "power_in"))
      (node (ref "R12") (pin "2") (pinfunction "2_2") (pintype "passive"))
    )
    (net (code "30") (name "Net-(Q3-C)") (class "Default")
      (node (ref "BZ1") (pin "1") (pinfunction "1_1") (pintype "passive"))
      (node (ref "Q3") (pin "3") (pinfunction "C_3") (pintype "power_in"))
    )
    (net (code "31") (name "Net-(Q4-B)") (class "Default")
      (node (ref "Q4") (pin "1") (pinfunction "B_1") (pintype "power_in"))
      (node (ref "R22") (pin "2") (pinfunction "2_2") (pintype "passive"))
    )
    (net (code "32") (name "Net-(R14-Pad1)") (class "Default")
      (node (ref "R14") (pin "1") (pinfunction "1_1") (pintype "passive"))
      (node (ref "SW1") (pin "1") (pinfunction "1_1") (pintype "passive"))
    )
    (net (code "33") (name "Net-(R15-Pad2)") (class "Default")
      (node (ref "R15") (pin "2") (pinfunction "2_2") (pintype "passive"))
      (node (ref "SW1") (pin "2") (pinfunction "2_2") (pintype "passive"))
    )
    (net (code "34") (name "Net-(U4-BOOT0)") (class "Default")
      (node (ref "R10") (pin "2") (pinfunction "2_2") (pintype "passive"))
      (node (ref "U4") (pin "44") (pinfunction "BOOT0_44") (pintype "passive"))
    )
    (net (code "35") (name "Net-(U4-OSC_IN)") (class "Default")
      (node (ref "C15") (pin "2") (pinfunction "2_2") (pintype "passive"))
      (node (ref "U4") (pin "5") (pinfunction "OSC_IN_5") (pintype "passive"))
      (node (ref "X1") (pin "3") (pinfunction "3_3") (pintype "passive"))
    )
    (net (code "36") (name "Net-(U4-OSC_OUT)") (class "Default")
      (node (ref "C16") (pin "2") (pinfunction "2_2") (pintype "passive"))
      (node (ref "U4") (pin "6") (pinfunction "OSC_OUT_6") (pintype "passive"))
      (node (ref "X1") (pin "1") (pinfunction "1_1") (pintype "passive"))
    )
    (net (code "37") (name "Net-(U4-PB0)") (class "Default")
      (node (ref "R8") (pin "1") (pinfunction "1_1") (pintype "passive"))
      (node (ref "U4") (pin "18") (pinfunction "PB0_18") (pintype "passive"))
    )
    (net (code "38") (name "Net-(U4-PB14)") (class "Default")
      (node (ref "R11") (pin "1") (pinfunction "1_1") (pintype "passive"))
      (node (ref "U4") (pin "27") (pinfunction "PB14_27") (pintype "passive"))
    )
    (net (code "39") (name "Net-(U5-OSC_IN)") (class "Default")
      (node (ref "U5") (pin "1") (pinfunction "OSC_IN_1") (pintype "passive"))
      (node (ref "X2") (pin "2") (pinfunction "2_2") (pintype "passive"))
    )
    (net (code "40") (name "Net-(U5-OSC_OUT)") (class "Default")
      (node (ref "U5") (pin "2") (pinfunction "OSC_OUT_2") (pintype "passive"))
      (node (ref "X2") (pin "1") (pinfunction "1_1") (pintype "passive"))
    )
    (net (code "41") (name "Net-(U5-VBAT)") (class "Default")
      (node (ref "C28") (pin "1") (pinfunction "1_1") (pintype "passive"))
      (node (ref "D6") (pin "1") (pinfunction "1_1") (pintype "power_in"))
      (node (ref "U5") (pin "3") (pinfunction "VBAT_3") (pintype "passive"))
    )
    (net (code "42") (name "Net-(U7-SCLK)") (class "Default")
      (node (ref "R17") (pin "1") (pinfunction "1_1") (pintype "passive"))
      (node (ref "U7") (pin "1") (pinfunction "SCLK_1") (pintype "passive"))
    )
    (net (code "43") (name "Net-(U7-SIO)") (class "Default")
      (node (ref "R18") (pin "1") (pinfunction "1_1") (pintype "passive"))
      (node (ref "U7") (pin "3") (pinfunction "SIO_3") (pintype "passive"))
    )
    (net (code "44") (name "Net-(U7-~{CS})") (class "Default")
      (node (ref "R20") (pin "1") (pinfunction "1_1") (pintype "passive"))
      (node (ref "U7") (pin "2") (pinfunction "~{CS}_2") (pintype "passive"))
    )
    (net (code "45") (name "Net-(U7-~{OT})") (class "Default")
      (node (ref "R21") (pin "1") (pinfunction "1_1") (pintype "passive"))
      (node (ref "U7") (pin "5") (pinfunction "~{OT}_5") (pintype "passive"))
    )
    (net (code "46") (name "unconnected-(SW1-Pad3)") (class "Default")
      (node (ref "SW1") (pin "3") (pinfunction "3_3") (pintype "passive"))
    )
    (net (code "47") (name "unconnected-(U4-OSC32_IN-Pad3)") (class "Default")
      (node (ref "U4") (pin "3") (pinfunction "OSC32_IN_3") (pintype "passive"))
    )
    (net (code "48") (name "unconnected-(U4-OSC32_OUT-Pad4)") (class "Default")
      (node (ref "U4") (pin "4") (pinfunction "OSC32_OUT_4") (pintype "passive"))
    )
    (net (code "49") (name "unconnected-(U4-PA0_{slash}_WKP-Pad10)") (class "Default")
      (node (ref "U4") (pin "10") (pinfunction "PA0_/_WKP_10") (pintype "passive"))
    )
    (net (code "50") (name "unconnected-(U4-PA1-Pad11)") (class "Default")
      (node (ref "U4") (pin "11") (pinfunction "PA1_11") (pintype "passive"))
    )
    (net (code "51") (name "unconnected-(U4-PB3-Pad39)") (class "Default")
      (node (ref "U4") (pin "39") (pinfunction "PB3_39") (pintype "passive"))
    )
    (net (code "52") (name "unconnected-(U4-PB8-Pad45)") (class "Default")
      (node (ref "U4") (pin "45") (pinfunction "PB8_45") (pintype "passive"))
    )
    (net (code "53") (name "unconnected-(U4-PB12-Pad25)") (class "Default")
      (node (ref "U4") (pin "25") (pinfunction "PB12_25") (pintype "passive"))
    )
    (net (code "54") (name "unconnected-(U4-PB13-Pad26)") (class "Default")
      (node (ref "U4") (pin "26") (pinfunction "PB13_26") (pintype "passive"))
    )
    (net (code "55") (name "unconnected-(U4-PB15-Pad28)") (class "Default")
      (node (ref "U4") (pin "28") (pinfunction "PB15_28") (pintype "passive"))
    )
    (net (code "56") (name "unconnected-(U4-PC13-Pad2)") (class "Default")
      (node (ref "U4") (pin "2") (pinfunction "PC13_2") (pintype "passive"))
    )
    (net (code "57") (name "unconnected-(U4-SPI_MISO-Pad16)") (class "Default")
      (node (ref "U4") (pin "16") (pinfunction "SPI_MISO_16") (pintype "passive"))
    )
    (net (code "58") (name "unconnected-(U4-UART_CK-Pad29)") (class "Default")
      (node (ref "U4") (pin "29") (pinfunction "UART_CK_29") (pintype "passive"))
    )
    (net (code "59") (name "unconnected-(U4-UART_RX-Pad31)") (class "Default")
      (node (ref "U4") (pin "31") (pinfunction "UART_RX_31") (pintype "passive"))
    )
    (net (code "60") (name "unconnected-(U4-UART_TX-Pad30)") (class "Default")
      (node (ref "U4") (pin "30") (pinfunction "UART_TX_30") (pintype "passive"))
    )
    (net (code "61") (name "unconnected-(U4-VBAT-Pad1)") (class "Default")
      (node (ref "U4") (pin "1") (pinfunction "VBAT_1") (pintype "passive"))
    )
    (net (code "62") (name "unconnected-(U5-FT{slash}OUT-Pad7)") (class "Default")
      (node (ref "U5") (pin "7") (pinfunction "FT/OUT_7") (pintype "passive"))
    )
    (net (code "63") (name "unconnected-(U6-CLK-Pad20)") (class "Default")
      (node (ref "U6") (pin "20") (pinfunction "CLK_20") (pintype "passive"))
    )
    (net (code "64") (name "unconnected-(U6-CMD-Pad19)") (class "Default")
      (node (ref "U6") (pin "19") (pinfunction "CMD_19") (pintype "passive"))
    )
    (net (code "65") (name "unconnected-(U6-IO0-Pad25)") (class "Default")
      (node (ref "U6") (pin "25") (pinfunction "IO0_25") (pintype "passive"))
    )
    (net (code "66") (name "unconnected-(U6-IO2-Pad24)") (class "Default")
      (node (ref "U6") (pin "24") (pinfunction "IO2_24") (pintype "passive"))
    )
    (net (code "67") (name "unconnected-(U6-IO4-Pad26)") (class "Default")
      (node (ref "U6") (pin "26") (pinfunction "IO4_26") (pintype "passive"))
    )
    (net (code "68") (name "unconnected-(U6-IO5-Pad29)") (class "Default")
      (node (ref "U6") (pin "29") (pinfunction "IO5_29") (pintype "passive"))
    )
    (net (code "69") (name "unconnected-(U6-IO12-Pad14)") (class "Default")
      (node (ref "U6") (pin "14") (pinfunction "IO12_14") (pintype "passive"))
    )
    (net (code "70") (name "unconnected-(U6-IO13-Pad16)") (class "Default")
      (node (ref "U6") (pin "16") (pinfunction "IO13_16") (pintype "passive"))
    )
    (net (code "71") (name "unconnected-(U6-IO14-Pad13)") (class "Default")
      (node (ref "U6") (pin "13") (pinfunction "IO14_13") (pintype "passive"))
    )
    (net (code "72") (name "unconnected-(U6-IO15-Pad23)") (class "Default")
      (node (ref "U6") (pin "23") (pinfunction "IO15_23") (pintype "passive"))
    )
    (net (code "73") (name "unconnected-(U6-IO16-Pad27)") (class "Default")
      (node (ref "U6") (pin "27") (pinfunction "IO16_27") (pintype "passive"))
    )
    (net (code "74") (name "unconnected-(U6-IO17-Pad28)") (class "Default")
      (node (ref "U6") (pin "28") (pinfunction "IO17_28") (pintype "passive"))
    )
    (net (code "75") (name "unconnected-(U6-IO18-Pad30)") (class "Default")
      (node (ref "U6") (pin "30") (pinfunction "IO18_30") (pintype "passive"))
    )
    (net (code "76") (name "unconnected-(U6-IO19-Pad31)") (class "Default")
      (node (ref "U6") (pin "31") (pinfunction "IO19_31") (pintype "passive"))
    )
    (net (code "77") (name "unconnected-(U6-IO21-Pad33)") (class "Default")
      (node (ref "U6") (pin "33") (pinfunction "IO21_33") (pintype "passive"))
    )
    (net (code "78") (name "unconnected-(U6-IO22-Pad36)") (class "Default")
      (node (ref "U6") (pin "36") (pinfunction "IO22_36") (pintype "passive"))
    )
    (net (code "79") (name "unconnected-(U6-IO23-Pad37)") (class "Default")
      (node (ref "U6") (pin "37") (pinfunction "IO23_37") (pintype "passive"))
    )
    (net (code "80") (name "unconnected-(U6-IO25-Pad10)") (class "Default")
      (node (ref "U6") (pin "10") (pinfunction "IO25_10") (pintype "passive"))
    )
    (net (code "81") (name "unconnected-(U6-IO26-Pad11)") (class "Default")
      (node (ref "U6") (pin "11") (pinfunction "IO26_11") (pintype "passive"))
    )
    (net (code "82") (name "unconnected-(U6-IO27-Pad12)") (class "Default")
      (node (ref "U6") (pin "12") (pinfunction "IO27_12") (pintype "passive"))
    )
    (net (code "83") (name "unconnected-(U6-IO32-Pad8)") (class "Default")
      (node (ref "U6") (pin "8") (pinfunction "IO32_8") (pintype "passive"))
    )
    (net (code "84") (name "unconnected-(U6-IO33-Pad9)") (class "Default")
      (node (ref "U6") (pin "9") (pinfunction "IO33_9") (pintype "passive"))
    )
    (net (code "85") (name "unconnected-(U6-IO34-Pad6)") (class "Default")
      (node (ref "U6") (pin "6") (pinfunction "IO34_6") (pintype "passive"))
    )
    (net (code "86") (name "unconnected-(U6-IO35-Pad7)") (class "Default")
      (node (ref "U6") (pin "7") (pinfunction "IO35_7") (pintype "passive"))
    )
    (net (code "87") (name "unconnected-(U6-NC-Pad32)") (class "Default")
      (node (ref "U6") (pin "32") (pinfunction "NC_32") (pintype "passive"))
    )
    (net (code "88") (name "unconnected-(U6-SD0-Pad21)") (class "Default")
      (node (ref "U6") (pin "21") (pinfunction "SD0_21") (pintype "passive"))
    )
    (net (code "89") (name "unconnected-(U6-SD1-Pad22)") (class "Default")
      (node (ref "U6") (pin "22") (pinfunction "SD1_22") (pintype "passive"))
    )
    (net (code "90") (name "unconnected-(U6-SD2-Pad17)") (class "Default")
      (node (ref "U6") (pin "17") (pinfunction "SD2_17") (pintype "passive"))
    )
    (net (code "91") (name "unconnected-(U6-SD3-Pad18)") (class "Default")
      (node (ref "U6") (pin "18") (pinfunction "SD3_18") (pintype "passive"))
    )
    (net (code "92") (name "unconnected-(U6-SENSOR_VN-Pad5)") (class "Default")
      (node (ref "U6") (pin "5") (pinfunction "SENSOR_VN_5") (pintype "passive"))
    )
    (net (code "93") (name "unconnected-(U6-SENSOR_VP-Pad4)") (class "Default")
      (node (ref "U6") (pin "4") (pinfunction "SENSOR_VP_4") (pintype "passive"))
    )
    (net (code "94") (name "unconnected-(U7-NC-Pad7)") (class "Default")
      (node (ref "U7") (pin "7") (pinfunction "NC_7") (pintype "passive"))
    )
    (net (code "95") (name "unconnected-(U7-~{ALERT}-Pad6)") (class "Default")
      (node (ref "U7") (pin "6") (pinfunction "~{ALERT}_6") (pintype "passive"))
    )
  )
)
